# LTE_power_Rev01.net
KiCad netlist of a schematic drawn in Altium Designer
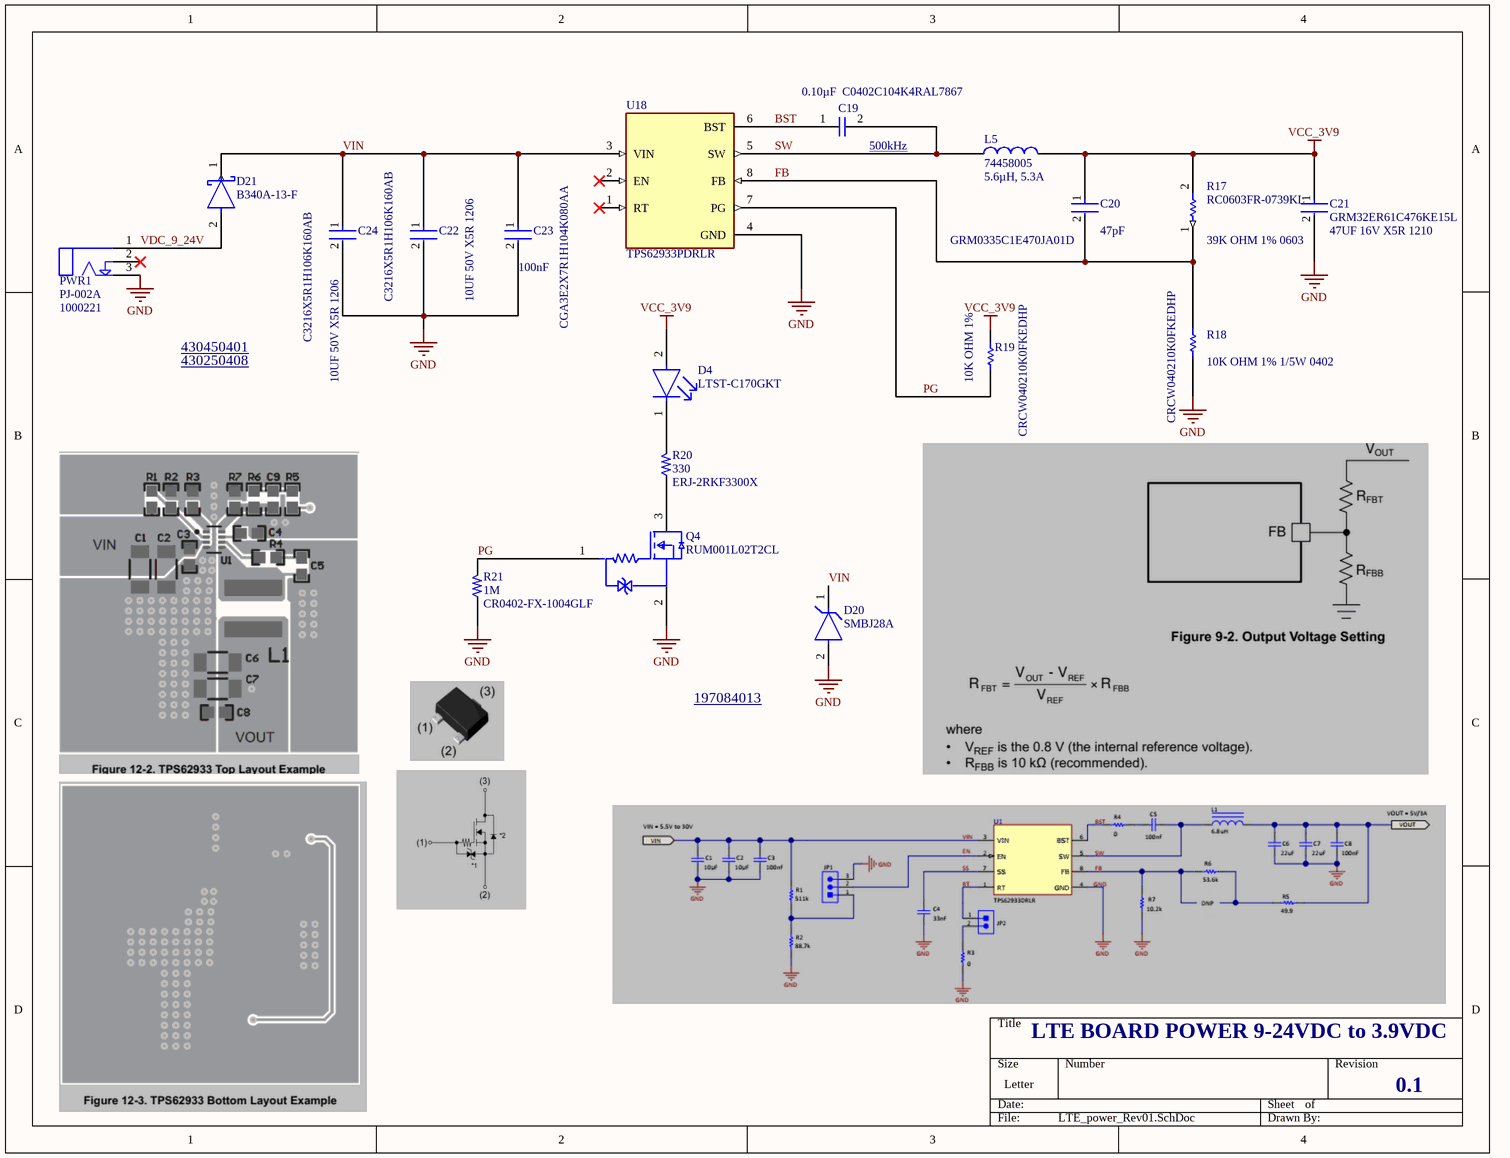
[diagram p0: LTE_power_Rev01.SchDoc]

(export (version "E")
  (design (tool "Eeschema 10.0.6"))
  (components
    (comp (ref "C19")
      (value "C0402C104K4RAL7867")
      (footprint "Passives:SMD CAP 1005")
      (description "0.1 µF ±10% 16V Ceramic Capacitor X7R 0402 (1005 Metric)")
      (fields
        (field (name "TOLERANCE") "±10%")
        (field (name "CAPACITANCE") "0.10µF")
        (field (name "PART_NUMBER") "1000742")
      )
      (libsource (lib "AltiumProductionDatabase") (part "C, 0.1 uF, 16V, 10%, X7R, 0402 CER"))
    )
    (comp (ref "C20")
      (value "GRM0335C1E470JA01D")
      (footprint "FP-GRM033-0_03-IPC_B")
      (description "47 pF ±5% 25V Ceramic Capacitor C0G, NP0 0201 (0603 Metric)")
      (fields
        (field (name "TOLERANCE") "5%")
        (field (name "CAPACITANCE") "47pF")
        (field (name "DIGI-KEY PART NUMBER") "490-1256-1-ND")
      )
      (libsource (lib "Altium Content Vault") (part "b4654b650e69147ec39a6b967a45e02"))
    )
    (comp (ref "C21")
      (value "GRM32ER61C476KE15L")
      (footprint "FP-GRM32E-0_3-0_2-IPC_C")
      (description "47 µF ±10% 16V Ceramic Capacitor X5R 1210 (3225 Metric)")
      (fields
        (field (name "VOLTAGE") "16V")
        (field (name "TOLERANCE") "10%")
        (field (name "CAPACITANCE") "47UF 16V X5R 1210")
      )
      (libsource (lib "Altium Content Vault") (part "b4654b650e69147ec39a6b967a45e02"))
    )
    (comp (ref "C22")
      (value "C3216X5R1H106K160AB")
      (footprint "FP-C3216-160-0_2-IPC_A")
      (description "10 µF ±10% 50V Ceramic Capacitor X5R 1206 (3216 Metric)")
      (fields
        (field (name "TOLERANCE") "10%")
        (field (name "VOLTAGE") "50V")
        (field (name "CAPACITANCE") "10UF 50V X5R 1206")
      )
      (libsource (lib "Altium Content Vault") (part "11868f565c42a9108669ba33697ecf6"))
    )
    (comp (ref "C23")
      (value "CGA3E2X7R1H104K080AA")
      (footprint "FP-CGA3E-0_3-0_1-IPC_A")
      (description "0.1 µF ±10% 50V Ceramic Capacitor X7R 0603 (1608 Metric)")
      (fields
        (field (name "TOLERANCE") "10%")
        (field (name "CAPACITANCE") "100nF")
        (field (name "VOLTAGE") "50V")
      )
      (libsource (lib "Altium Content Vault") (part "b4654b650e69147ec39a6b967a45e02"))
    )
    (comp (ref "C24")
      (value "C3216X5R1H106K160AB")
      (footprint "FP-C3216-160-0_2-IPC_A")
      (description "10 µF ±10% 50V Ceramic Capacitor X5R 1206 (3216 Metric)")
      (fields
        (field (name "TOLERANCE") "10%")
        (field (name "VOLTAGE") "50V")
        (field (name "CAPACITANCE") "10UF 50V X5R 1206")
      )
      (libsource (lib "Altium Content Vault") (part "11868f565c42a9108669ba33697ecf6"))
    )
    (comp (ref "D4")
      (value "LTST-C170GKT")
      (footprint "FP-LTST-C170GKT-MFG")
      (description "Green 569nm LED Indication - Discrete 2.1V 0805 (2012 Metric)")
      (fields (field (name "VOLTAGE") "5V") (field (name "DIGI-KEY PART NUMBER") "160-1179-1-ND"))
      (libsource (lib "Altium Content Vault") (part "8706943c75ba83719d021d2fdc84c58"))
    )
    (comp (ref "D20")
      (value "SMBJ28A")
      (footprint "FP-SMBJ-MFG")
      (description "45.4V Clamp 13.3A Ipp Tvs Diode Surface Mount DO-214AA (SMBJ)")
      (fields
        (field (name "MANUFACTURER") "Littelfuse Inc.")
        (field (name "OCTOPART") "https://octopart.com/smbj28a-littelfuse-350790")
      )
      (libsource (lib "Altium Content Vault") (part "f813f71cba58e380607f5dd3caf9714"))
    )
    (comp (ref "D21")
      (value "B340A-13-F")
      (footprint "FP-SMA-MFG")
      (description "Diode 40 V 3A Surface Mount SMA")
      (fields (field (name "VOLTAGE") "40V") (field (name "DIGI-KEY PART NUMBER") "B340A-FDICT-ND"))
      (libsource (lib "Altium Content Vault") (part "1d6ec82d83fb6aee721767c19dac4b9"))
    )
    (comp (ref "L5")
      (value "5.6µH, 5.3A")
      (footprint "WE-PD4_Type X")
      (fields
        (field (name "MANUFACTURER PART NUMBER") "74458005")
        (field (name "MANUFACTURER") "Wurth Elektronik")
        (field (name "DIGI-KEY PART NUMBER") "732-1380-1-ND")
        (field (name "ALTERNATIVE PART NUMBER") "NPI52W5R6MTRF")
      )
      (libsource (lib "WE-PD4 (rev22d)") (part "74458005"))
    )
    (comp (ref "PWR1")
      (value "PJ-202A")
      (footprint "PJ-202AH")
      (description "Power Barrel Connector Jack 2.10mm ID (0.083\"), 5.50mm OD (0.217\") Through Hole, Right Angle")
      (fields
        (field (name "MANUFACTURER_PART_NUMBER1") "PJ-002A")
        (field (name "PART_NUMBER") "1000221")
        (field (name "DIGIKEY PART NUMBER") "CP-202AH-ND")
        (field (name "MANUFACTURER") "Same Sky (Formerly CUI Devices)")
      )
      (libsource (lib "AltiumProductionDatabase") (part "PJ-202A"))
    )
    (comp (ref "Q4")
      (value "RUM001L02T2CL")
      (footprint "FP-VMT3-MFG")
      (description "N-Channel 20 V 100mA (Ta) 150mW (Ta) Surface Mount VMT3")
      (fields
        (field (name "DIGI-KEY PART NUMBER") "RUM001L02T2CLCT-ND")
        (field (name "MANUFACTURER") "Rohm Semiconductor")
      )
      (libsource (lib "MOSFET") (part "RUM001L02T2CL"))
    )
    (comp (ref "R17")
      (value "RC0603FR-0739KL")
      (footprint "RESC1608X55X25LL10T15")
      (description "39 kOhms ±1% 0.1W, 1/10W Chip Resistor 0603 (1608 Metric) Moisture Resistant Thick Film")
      (fields
        (field (name "RESISTANCE") "39K OHM 1% 0603")
        (field (name "TOLERANCE") "1%")
        (field (name "MANUFACTURER") "YAGEO")
      )
      (libsource (lib "Altium Content Vault") (part "RES-2"))
    )
    (comp (ref "R18")
      (value "CRCW040210K0FKEDHP")
      (footprint "RESC1005X40X25ML05T10")
      (fields
        (field (name "MANUFACTURER") "Vishay Dale")
        (field (name "DIGI-KEY PART NUMBER") "541-10.0KYCT-ND")
        (field (name "RESISTANCE") "10K OHM 1% 1/5W 0402")
      )
      (libsource (lib "Altium Content Vault") (part "RES"))
    )
    (comp (ref "R19")
      (value "CRCW040210K0FKEDHP")
      (footprint "RESC1005X40X25ML05T10")
      (fields
        (field (name "MANUFACTURER") "Vishay Dale")
        (field (name "DIGI-KEY PART NUMBER") "541-10.0KYCT-ND")
        (field (name "RESISTANCE") "10K OHM 1%")
      )
      (libsource (lib "Altium Content Vault") (part "RES"))
    )
    (comp (ref "R20")
      (value "ERJ-2RKF3300X")
      (footprint "SMD RES 1005")
      (description "330 Ohms ±1% 0.1W, 1/10W Chip Resistor 0402 (1005 Metric) Automotive AEC-Q200 Thick Film")
      (fields
        (field (name "PART_NUMBER") "1001162")
        (field (name "RESISTANCE") "330")
        (field (name "POWER") "0.1W, 1/10W")
        (field (name "MANUFACTURER PRODUCT NUMBER") "ERJ-2RKF3300X")
      )
      (libsource (lib "AltiumProductionDatabase") (part "R, 330, 1%, 1/10W, 0402"))
    )
    (comp (ref "R21")
      (value "CR0402-FX-1004GLF")
      (footprint "SMD RES 1005")
      (description "1 MOhms ±1% 0.063W, 1/16W Chip Resistor 0402 (1005 Metric) Thick Film")
      (fields
        (field (name "PART_NUMBER") "1000797")
        (field (name "RESISTANCE") "1M")
        (field (name "POWER") "0.063W, 1/16W")
        (field (name "MANUFACTURER PRODUCT NUMBER") "CR0402-FX-1004GLF")
      )
      (libsource (lib "AltiumProductionDatabase") (part "R, 1M, 1%, 1/16W, 0402"))
    )
    (comp (ref "U18")
      (value "TPS62933PDRLR")
      (footprint "SOFL50P160X60-8N")
      (description "Buck Switching Regulator IC Positive Adjustable 0.8V 1 Output 3A SOT-583")
      (fields
        (field (name "MF") "Texas Instruments")
        (field (name "DIGI-KEY PART NUMBER") "296-TPS62933PDRLRCT-ND")
      )
      (libsource (lib "TPS62933PDRLR") (part "TPS62933PDRLR"))
    )
  )
  (nets
    (net (code "1") (name "/BST") (class "Default")
      (node (ref "C19") (pin "1") (pinfunction "1_1") (pintype "passive"))
      (node (ref "U18") (pin "6") (pinfunction "BST_6") (pintype "power_in"))
    )
    (net (code "2") (name "/FB") (class "Default")
      (node (ref "C20") (pin "2") (pinfunction "2_2") (pintype "passive"))
      (node (ref "R17") (pin "1") (pinfunction "1_1") (pintype "output"))
      (node (ref "R18") (pin "2") (pinfunction "2_2") (pintype "passive"))
      (node (ref "U18") (pin "8") (pinfunction "FB_8") (pintype "input"))
    )
    (net (code "3") (name "/PG") (class "Default")
      (node (ref "Q4") (pin "1") (pinfunction "Gate_1") (pintype "passive"))
      (node (ref "R19") (pin "1") (pinfunction "1_1") (pintype "passive"))
      (node (ref "R21") (pin "2") (pinfunction "2_2") (pintype "passive"))
      (node (ref "U18") (pin "7") (pinfunction "PG_7") (pintype "output"))
    )
    (net (code "4") (name "/SW") (class "Default")
      (node (ref "C19") (pin "2") (pinfunction "2_2") (pintype "passive"))
      (node (ref "L5") (pin "1") (pinfunction "1_1") (pintype "passive"))
      (node (ref "U18") (pin "5") (pinfunction "SW_5") (pintype "output"))
    )
    (net (code "5") (name "/VDC_9_24V") (class "Default")
      (node (ref "D21") (pin "2") (pinfunction "A_2") (pintype "passive"))
      (node (ref "PWR1") (pin "1") (pinfunction "1_1") (pintype "passive"))
    )
    (net (code "6") (name "/VIN") (class "Default")
      (node (ref "C22") (pin "1") (pinfunction "1_1") (pintype "passive"))
      (node (ref "C23") (pin "1") (pinfunction "1_1") (pintype "passive"))
      (node (ref "C24") (pin "1") (pinfunction "1_1") (pintype "passive"))
      (node (ref "D20") (pin "1") (pinfunction "C_1") (pintype "passive"))
      (node (ref "D21") (pin "1") (pinfunction "C_1") (pintype "output"))
      (node (ref "U18") (pin "3") (pinfunction "VIN_3") (pintype "input"))
    )
    (net (code "7") (name "GND") (class "Default")
      (node (ref "C21") (pin "2") (pinfunction "2_2") (pintype "passive"))
      (node (ref "C22") (pin "2") (pinfunction "2_2") (pintype "passive"))
      (node (ref "C23") (pin "2") (pinfunction "2_2") (pintype "passive"))
      (node (ref "C24") (pin "2") (pinfunction "2_2") (pintype "passive"))
      (node (ref "D20") (pin "2") (pinfunction "A_2") (pintype "passive"))
      (node (ref "PWR1") (pin "3") (pinfunction "3_3") (pintype "passive"))
      (node (ref "Q4") (pin "2") (pinfunction "Source_2") (pintype "passive"))
      (node (ref "R18") (pin "1") (pinfunction "1_1") (pintype "passive"))
      (node (ref "R21") (pin "1") (pinfunction "1_1") (pintype "passive"))
      (node (ref "U18") (pin "4") (pinfunction "GND_4") (pintype "power_in"))
    )
    (net (code "8") (name "Net-(D4-C)") (class "Default")
      (node (ref "D4") (pin "1") (pinfunction "C_1") (pintype "passive"))
      (node (ref "R20") (pin "2") (pinfunction "2_2") (pintype "passive"))
    )
    (net (code "9") (name "Net-(Q4-Drain)") (class "Default")
      (node (ref "Q4") (pin "3") (pinfunction "Drain_3") (pintype "passive"))
      (node (ref "R20") (pin "1") (pinfunction "1_1") (pintype "passive"))
    )
    (net (code "10") (name "VCC_3V9") (class "Default")
      (node (ref "C20") (pin "1") (pinfunction "1_1") (pintype "passive"))
      (node (ref "C21") (pin "1") (pinfunction "1_1") (pintype "passive"))
      (node (ref "D4") (pin "2") (pinfunction "A_2") (pintype "passive"))
      (node (ref "L5") (pin "2") (pinfunction "2_2") (pintype "passive"))
      (node (ref "R17") (pin "2") (pinfunction "2_2") (pintype "passive"))
      (node (ref "R19") (pin "2") (pinfunction "2_2") (pintype "passive"))
    )
    (net (code "11") (name "unconnected-(PWR1-Pad2)") (class "Default")
      (node (ref "PWR1") (pin "2") (pinfunction "2_2") (pintype "passive+no_connect"))
    )
    (net (code "12") (name "unconnected-(U18-EN-Pad2)") (class "Default")
      (node (ref "U18") (pin "2") (pinfunction "EN_2") (pintype "input+no_connect"))
    )
    (net (code "13") (name "unconnected-(U18-RT-Pad1)") (class "Default")
      (node (ref "U18") (pin "1") (pinfunction "RT_1") (pintype "input+no_connect"))
    )
  )
)
